# Famicom_PWR_AV_Board.net
KiCad netlist of a schematic drawn in EAGLE
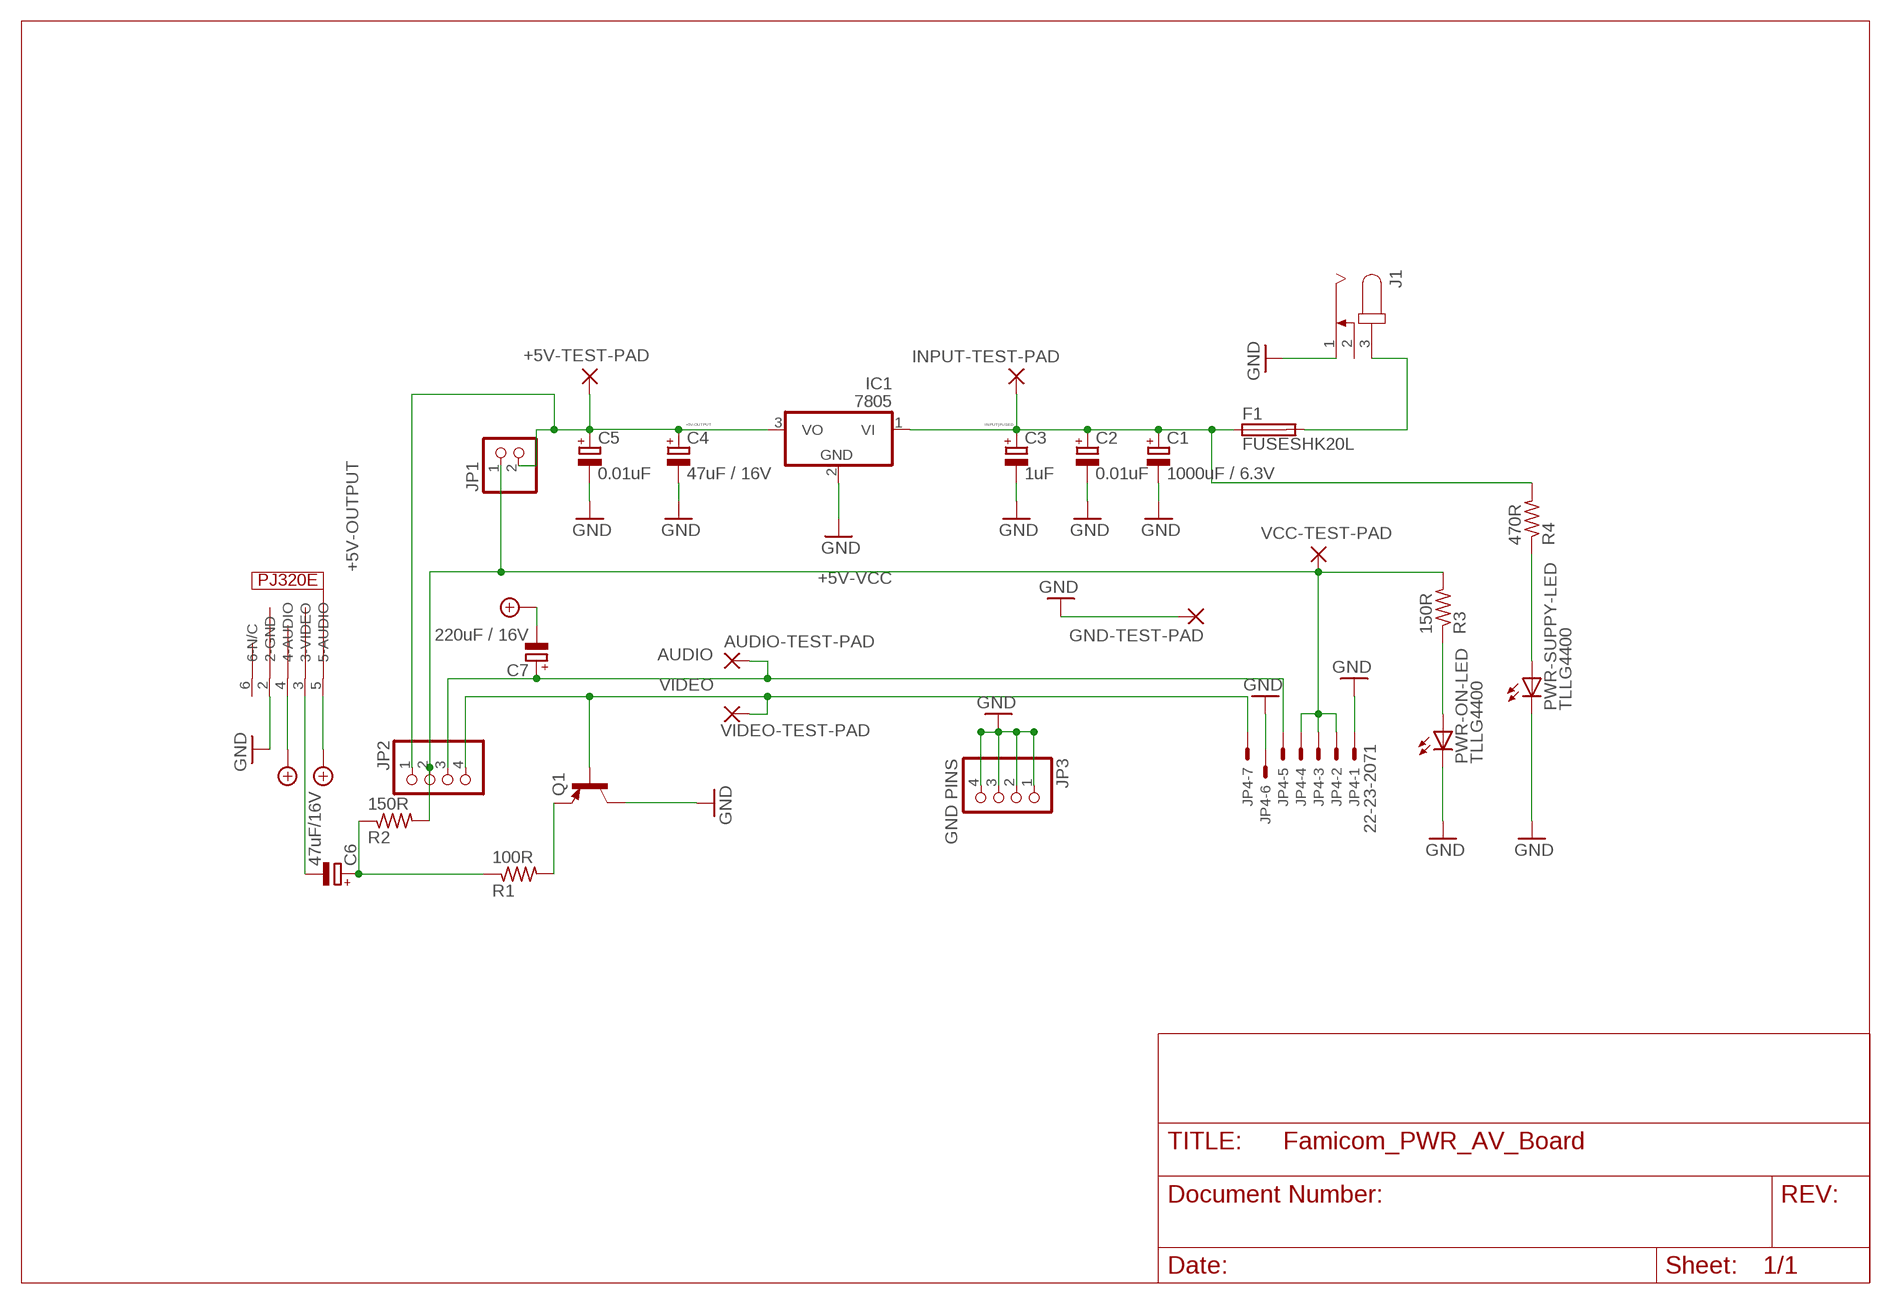
[diagram p0: schematic, sheet 1]

(export (version "E")
  (design (tool "Eeschema 10.0.6"))
  (components
    (comp (ref "+5V-TEST-PAD")
      (value "WIREPAD2,15/1,0")
      (footprint "eagle-import:2,15_1,0")
      (libsource (lib "eagle-import") (part "WIREPAD2,15/1,0"))
    )
    (comp (ref "AUDIO-TEST-PAD")
      (value "WIREPAD2,15/1,0")
      (footprint "eagle-import:2,15_1,0")
      (libsource (lib "eagle-import") (part "WIREPAD2,15/1,0"))
    )
    (comp (ref "C1")
      (value "1000uF / 6.3V")
      (footprint "eagle-import:TAP5-45")
      (libsource (lib "eagle-import") (part "CPOL-EUTAP5-45"))
    )
    (comp (ref "C2")
      (value "0.01uF")
      (footprint "eagle-import:TAP5-45")
      (libsource (lib "eagle-import") (part "CPOL-EUTAP5-45"))
    )
    (comp (ref "C3")
      (value "1uF")
      (footprint "eagle-import:TAP5-45")
      (libsource (lib "eagle-import") (part "CPOL-EUTAP5-45"))
    )
    (comp (ref "C4")
      (value "47uF / 16V")
      (footprint "eagle-import:TAP5-45")
      (libsource (lib "eagle-import") (part "CPOL-EUTAP5-45"))
    )
    (comp (ref "C5")
      (value "0.01uF")
      (footprint "eagle-import:TAP5-45")
      (libsource (lib "eagle-import") (part "CPOL-EUTAP5-45"))
    )
    (comp (ref "C6")
      (value "47uF/16V")
      (footprint "eagle-import:TAP5-45")
      (libsource (lib "eagle-import") (part "CPOL-EUTAP5-45"))
    )
    (comp (ref "C7")
      (value "220uF / 16V")
      (footprint "eagle-import:TAP5-45")
      (libsource (lib "eagle-import") (part "CPOL-EUTAP5-45"))
    )
    (comp (ref "F1")
      (value "FUSESHK20L")
      (footprint "eagle-import:SHK20L")
      (libsource (lib "eagle-import") (part "FUSESHK20L"))
    )
    (comp (ref "GND-TEST-PAD")
      (value "WIREPAD2,15/1,0")
      (footprint "eagle-import:2,15_1,0")
      (libsource (lib "eagle-import") (part "WIREPAD2,15/1,0"))
    )
    (comp (ref "IC1")
      (value "7805")
      (footprint "eagle-import:TO220V")
      (libsource (lib "eagle-import") (part "78TV05"))
    )
    (comp (ref "INPUT-TEST-PAD")
      (value "WIREPAD2,15/1,0")
      (footprint "eagle-import:2,15_1,0")
      (libsource (lib "eagle-import") (part "WIREPAD2,15/1,0"))
    )
    (comp (ref "J1")
      (value "JACK-PLUG0")
      (footprint "eagle-import:SPC4077")
      (libsource (lib "eagle-import") (part "JACK-PLUG0"))
    )
    (comp (ref "JP1")
      (value "PINHD-1X2")
      (footprint "eagle-import:1X02")
      (libsource (lib "eagle-import") (part "PINHD-1X2"))
    )
    (comp (ref "JP2")
      (value "PINHD-1X4")
      (footprint "eagle-import:1X04")
      (libsource (lib "eagle-import") (part "PINHD-1X4"))
    )
    (comp (ref "JP3")
      (value "GND PINS")
      (footprint "eagle-import:1X04")
      (libsource (lib "eagle-import") (part "PINHD-1X4"))
    )
    (comp (ref "JP4")
      (value "22-23-2071")
      (footprint "eagle-import:22-23-2071")
      (fields (field (name "MF") "MOLEX"))
      (libsource (lib "eagle-import") (part "22-23-2071"))
    )
    (comp (ref "PWR-ON-LED")
      (value "TLLG4400")
      (footprint "eagle-import:LED3MM")
      (fields (field (name "MF") "VISHAY SEMICONDUCTOR"))
      (libsource (lib "eagle-import") (part "TLLG4400"))
    )
    (comp (ref "PWR-SUPPY-LED")
      (value "TLLG4400")
      (footprint "eagle-import:LED3MM")
      (fields (field (name "MF") "VISHAY SEMICONDUCTOR"))
      (libsource (lib "eagle-import") (part "TLLG4400"))
    )
    (comp (ref "Q1")
      (value "MPSA56-TO92")
      (footprint "eagle-import:TO92-CBE")
      (libsource (lib "eagle-import") (part "-?TO92MPSA56"))
    )
    (comp (ref "R1")
      (value "100R")
      (footprint "eagle-import:0204_7")
      (libsource (lib "eagle-import") (part "R-US_0204/7"))
    )
    (comp (ref "R2")
      (value "150R")
      (footprint "eagle-import:0204_7")
      (libsource (lib "eagle-import") (part "R-US_0204/7"))
    )
    (comp (ref "R3")
      (value "150R")
      (footprint "eagle-import:0204_7")
      (libsource (lib "eagle-import") (part "R-US_0204/7"))
    )
    (comp (ref "R4")
      (value "470R")
      (footprint "eagle-import:0204_7")
      (libsource (lib "eagle-import") (part "R-US_0204/7"))
    )
    (comp (ref "U$2")
      (value "PJ320E")
      (footprint "eagle-import:PJ320E")
      (libsource (lib "eagle-import") (part "PJ320E"))
    )
    (comp (ref "VCC-TEST-PAD")
      (value "WIREPAD2,15/1,0")
      (footprint "eagle-import:2,15_1,0")
      (libsource (lib "eagle-import") (part "WIREPAD2,15/1,0"))
    )
    (comp (ref "VIDEO-TEST-PAD")
      (value "WIREPAD2,15/1,0")
      (footprint "eagle-import:2,15_1,0")
      (libsource (lib "eagle-import") (part "WIREPAD2,15/1,0"))
    )
  )
  (nets
    (net (code "1") (name "+5V") (class "Default")
      (node (ref "C7") (pin "-") (pinfunction "-_-") (pintype "passive"))
      (node (ref "U$2") (pin "4") (pinfunction "4-AUDIO_4") (pintype "bidirectional"))
      (node (ref "U$2") (pin "5") (pinfunction "5-AUDIO_5") (pintype "bidirectional"))
    )
    (net (code "2") (name "/+5V-OUTPUT") (class "Default")
      (node (ref "+5V-TEST-PAD") (pin "1") (pinfunction "P_1") (pintype "passive"))
      (node (ref "C4") (pin "+") (pinfunction "+_+") (pintype "passive"))
      (node (ref "C5") (pin "+") (pinfunction "+_+") (pintype "passive"))
      (node (ref "IC1") (pin "3") (pinfunction "VO_3") (pintype "passive"))
      (node (ref "JP1") (pin "2") (pinfunction "2_2") (pintype "passive"))
      (node (ref "JP2") (pin "1") (pinfunction "1_1") (pintype "passive"))
    )
    (net (code "3") (name "/+5V-VCC") (class "Default")
      (node (ref "JP1") (pin "1") (pinfunction "1_1") (pintype "passive"))
      (node (ref "JP2") (pin "2") (pinfunction "2_2") (pintype "passive"))
      (node (ref "JP4") (pin "2") (pinfunction "S_2") (pintype "passive"))
      (node (ref "JP4") (pin "3") (pinfunction "S_3") (pintype "passive"))
      (node (ref "JP4") (pin "4") (pinfunction "S_4") (pintype "passive"))
      (node (ref "R2") (pin "2") (pinfunction "2_2") (pintype "passive"))
      (node (ref "R3") (pin "2") (pinfunction "2_2") (pintype "passive"))
      (node (ref "VCC-TEST-PAD") (pin "1") (pinfunction "P_1") (pintype "passive"))
    )
    (net (code "4") (name "/AUDIO") (class "Default")
      (node (ref "AUDIO-TEST-PAD") (pin "1") (pinfunction "P_1") (pintype "passive"))
      (node (ref "C7") (pin "+") (pinfunction "+_+") (pintype "passive"))
      (node (ref "JP2") (pin "3") (pinfunction "3_3") (pintype "passive"))
      (node (ref "JP4") (pin "5") (pinfunction "S_5") (pintype "passive"))
    )
    (net (code "5") (name "/INPUT|FUSED") (class "Default")
      (node (ref "C1") (pin "+") (pinfunction "+_+") (pintype "passive"))
      (node (ref "C2") (pin "+") (pinfunction "+_+") (pintype "passive"))
      (node (ref "C3") (pin "+") (pinfunction "+_+") (pintype "passive"))
      (node (ref "F1") (pin "1A") (pinfunction "1_1A") (pintype "passive"))
      (node (ref "IC1") (pin "1") (pinfunction "VI_1") (pintype "input"))
      (node (ref "INPUT-TEST-PAD") (pin "1") (pinfunction "P_1") (pintype "passive"))
      (node (ref "R4") (pin "2") (pinfunction "2_2") (pintype "passive"))
    )
    (net (code "6") (name "/VIDEO") (class "Default")
      (node (ref "JP2") (pin "4") (pinfunction "4_4") (pintype "passive"))
      (node (ref "JP4") (pin "7") (pinfunction "S_7") (pintype "passive"))
      (node (ref "Q1") (pin "B") (pinfunction "B_B") (pintype "passive"))
      (node (ref "VIDEO-TEST-PAD") (pin "1") (pinfunction "P_1") (pintype "passive"))
    )
    (net (code "7") (name "GND") (class "Default")
      (node (ref "C1") (pin "-") (pinfunction "-_-") (pintype "passive"))
      (node (ref "C2") (pin "-") (pinfunction "-_-") (pintype "passive"))
      (node (ref "C3") (pin "-") (pinfunction "-_-") (pintype "passive"))
      (node (ref "C4") (pin "-") (pinfunction "-_-") (pintype "passive"))
      (node (ref "C5") (pin "-") (pinfunction "-_-") (pintype "passive"))
      (node (ref "GND-TEST-PAD") (pin "1") (pinfunction "P_1") (pintype "passive"))
      (node (ref "IC1") (pin "2") (pinfunction "GND_2") (pintype "passive"))
      (node (ref "J1") (pin "1") (pinfunction "1_1") (pintype "passive"))
      (node (ref "JP3") (pin "1") (pinfunction "1_1") (pintype "passive"))
      (node (ref "JP3") (pin "2") (pinfunction "2_2") (pintype "passive"))
      (node (ref "JP3") (pin "3") (pinfunction "3_3") (pintype "passive"))
      (node (ref "JP3") (pin "4") (pinfunction "4_4") (pintype "passive"))
      (node (ref "JP4") (pin "1") (pinfunction "S_1") (pintype "passive"))
      (node (ref "JP4") (pin "6") (pinfunction "S_6") (pintype "passive"))
      (node (ref "PWR-ON-LED") (pin "K") (pinfunction "C_K") (pintype "passive"))
      (node (ref "PWR-SUPPY-LED") (pin "K") (pinfunction "C_K") (pintype "passive"))
      (node (ref "Q1") (pin "C") (pinfunction "C_C") (pintype "passive"))
      (node (ref "U$2") (pin "2") (pinfunction "2-GND_2") (pintype "bidirectional"))
    )
    (net (code "8") (name "Net-(C6-Pad+)") (class "Default")
      (node (ref "C6") (pin "+") (pinfunction "+_+") (pintype "passive"))
      (node (ref "R1") (pin "1") (pinfunction "1_1") (pintype "passive"))
      (node (ref "R2") (pin "1") (pinfunction "1_1") (pintype "passive"))
    )
    (net (code "9") (name "Net-(F1-2)") (class "Default")
      (node (ref "F1") (pin "2A") (pinfunction "2_2A") (pintype "passive"))
      (node (ref "J1") (pin "3") (pinfunction "3_3") (pintype "passive"))
    )
    (net (code "10") (name "Net-(PWR-ON-LED-PadA)") (class "Default")
      (node (ref "PWR-ON-LED") (pin "A") (pinfunction "A_A") (pintype "passive"))
      (node (ref "R3") (pin "1") (pinfunction "1_1") (pintype "passive"))
    )
    (net (code "11") (name "Net-(PWR-SUPPY-LED-PadA)") (class "Default")
      (node (ref "PWR-SUPPY-LED") (pin "A") (pinfunction "A_A") (pintype "passive"))
      (node (ref "R4") (pin "1") (pinfunction "1_1") (pintype "passive"))
    )
    (net (code "12") (name "Net-(Q1-PadE)") (class "Default")
      (node (ref "Q1") (pin "E") (pinfunction "E_E") (pintype "passive"))
      (node (ref "R1") (pin "2") (pinfunction "2_2") (pintype "passive"))
    )
    (net (code "13") (name "Net-(U$2-3-VIDEO)") (class "Default")
      (node (ref "C6") (pin "-") (pinfunction "-_-") (pintype "passive"))
      (node (ref "U$2") (pin "3") (pinfunction "3-VIDEO_3") (pintype "bidirectional"))
    )
    (net (code "14") (name "unconnected-(J1-Pad2)") (class "Default")
      (node (ref "J1") (pin "2") (pinfunction "2_2") (pintype "passive"))
    )
    (net (code "15") (name "unconnected-(U$2-6-N{slash}C-Pad6)") (class "Default")
      (node (ref "U$2") (pin "6") (pinfunction "6-N/C_6") (pintype "no_connect"))
    )
  )
)
